# mpx4115-breakout.net
KiCad netlist of a schematic drawn in EAGLE
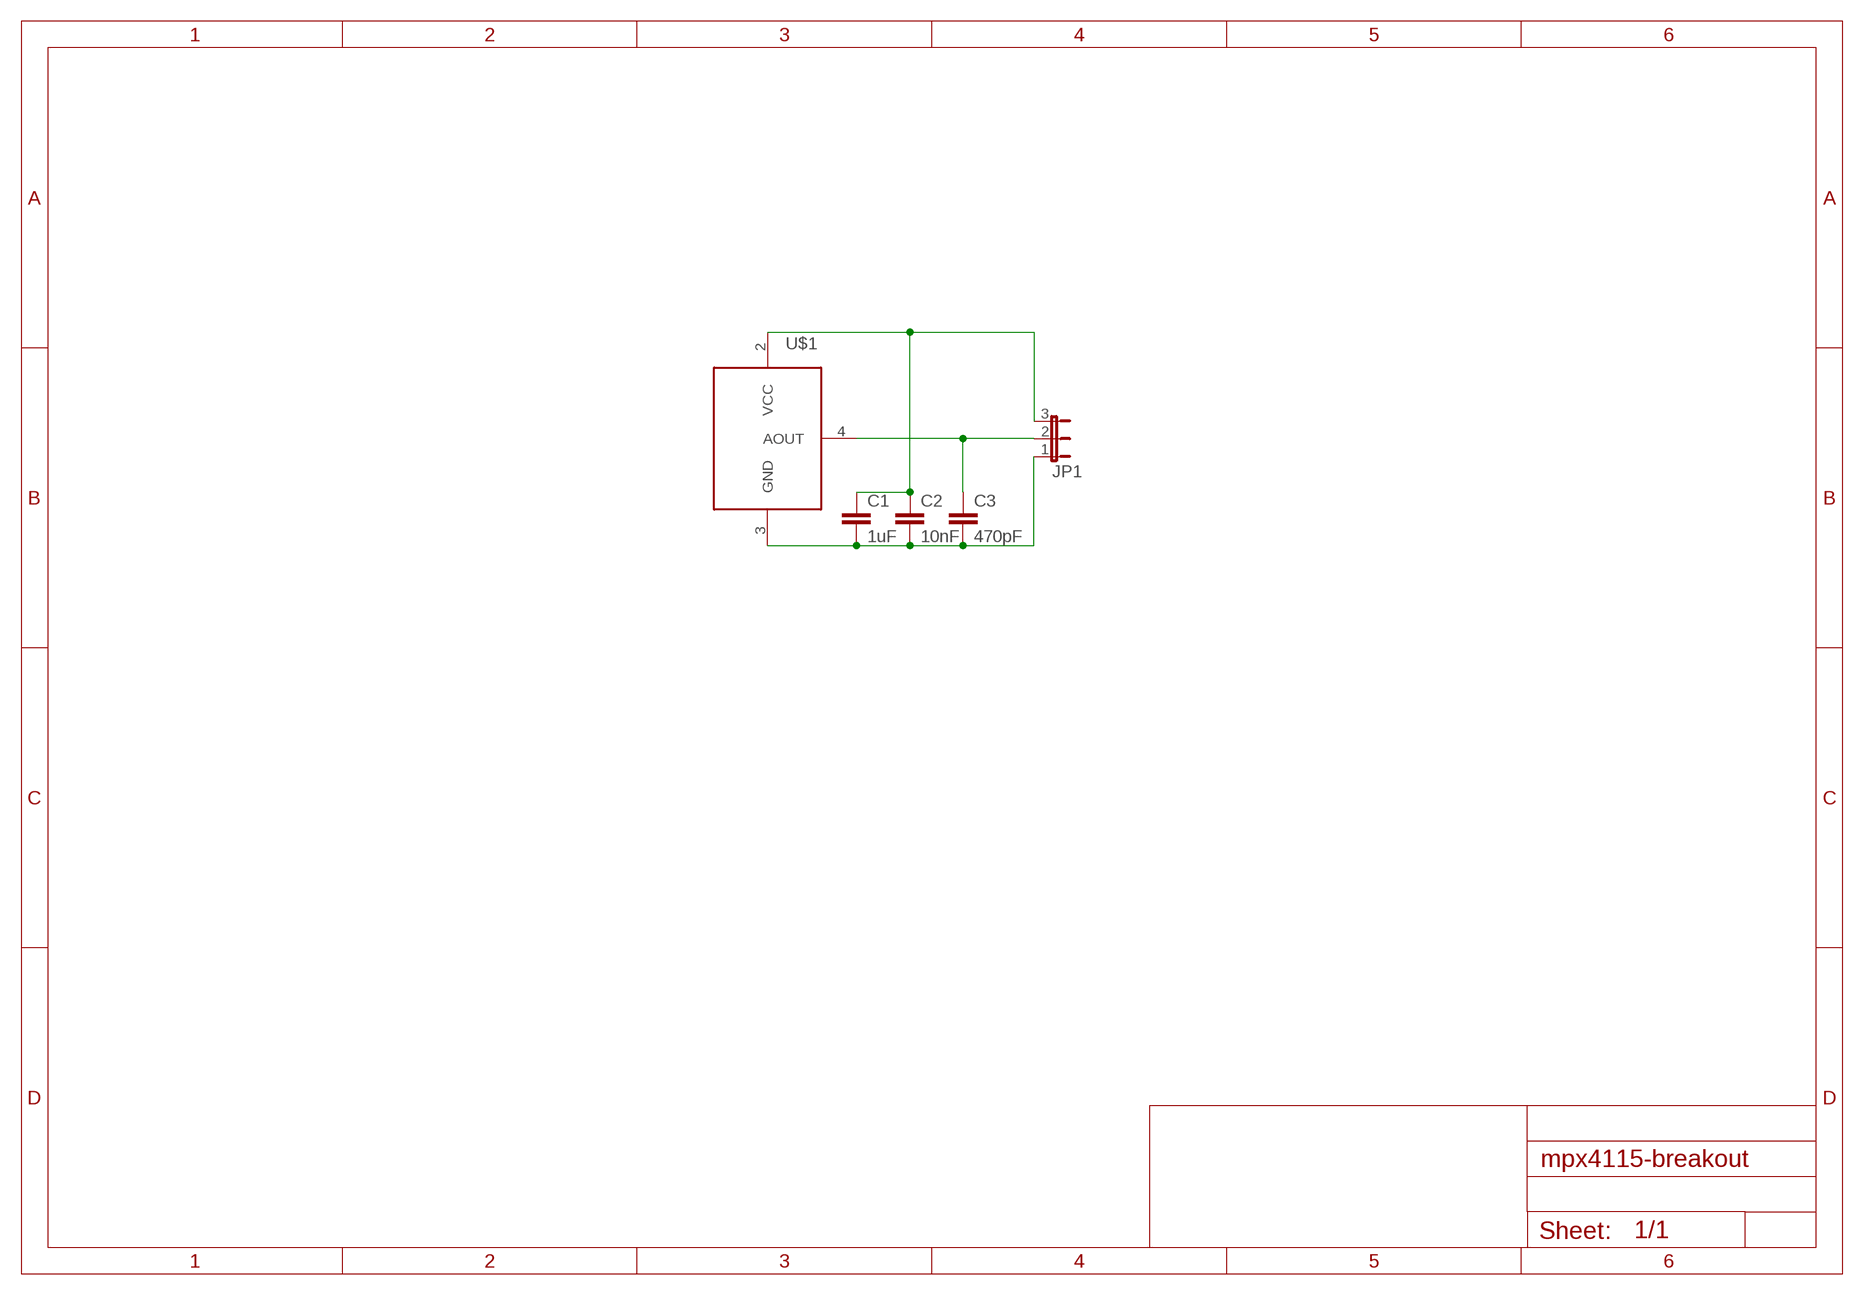
[diagram p0: schematic, sheet 1]

(export (version "E")
  (design (tool "Eeschema 10.0.6"))
  (components
    (comp (ref "C1")
      (value "1uF")
      (footprint "eagle-import:C0805")
      (libsource (lib "eagle-import") (part "C-EUC0805"))
    )
    (comp (ref "C2")
      (value "10nF")
      (footprint "eagle-import:C0805")
      (libsource (lib "eagle-import") (part "C-EUC0805"))
    )
    (comp (ref "C3")
      (value "470pF")
      (footprint "eagle-import:C0805")
      (libsource (lib "eagle-import") (part "C-EUC0805"))
    )
    (comp (ref "JP1")
      (value "JP2E")
      (footprint "eagle-import:JP2")
      (libsource (lib "eagle-import") (part "JP2E"))
    )
    (comp (ref "U$1")
      (value "MPX4115A")
      (footprint "eagle-import:MPX4115A")
      (libsource (lib "eagle-import") (part "MPX4115A"))
    )
  )
  (nets
    (net (code "1") (name "Net-(U$1-AOUT)") (class "Default")
      (node (ref "C3") (pin "1") (pinfunction "1_1") (pintype "passive"))
      (node (ref "JP1") (pin "2") (pinfunction "2_2") (pintype "passive"))
      (node (ref "U$1") (pin "4") (pinfunction "AOUT_4") (pintype "output"))
    )
    (net (code "2") (name "Net-(U$1-GND)") (class "Default")
      (node (ref "C1") (pin "2") (pinfunction "2_2") (pintype "passive"))
      (node (ref "C2") (pin "2") (pinfunction "2_2") (pintype "passive"))
      (node (ref "C3") (pin "2") (pinfunction "2_2") (pintype "passive"))
      (node (ref "JP1") (pin "1") (pinfunction "1_1") (pintype "passive"))
      (node (ref "U$1") (pin "3") (pinfunction "GND_3") (pintype "bidirectional"))
    )
    (net (code "3") (name "Net-(U$1-VCC)") (class "Default")
      (node (ref "C1") (pin "1") (pinfunction "1_1") (pintype "passive"))
      (node (ref "C2") (pin "1") (pinfunction "1_1") (pintype "passive"))
      (node (ref "JP1") (pin "3") (pinfunction "3_3") (pintype "passive"))
      (node (ref "U$1") (pin "2") (pinfunction "VCC_2") (pintype "power_in"))
    )
  )
)
